# source_eagle.net
KiCad netlist of a schematic drawn in EAGLE
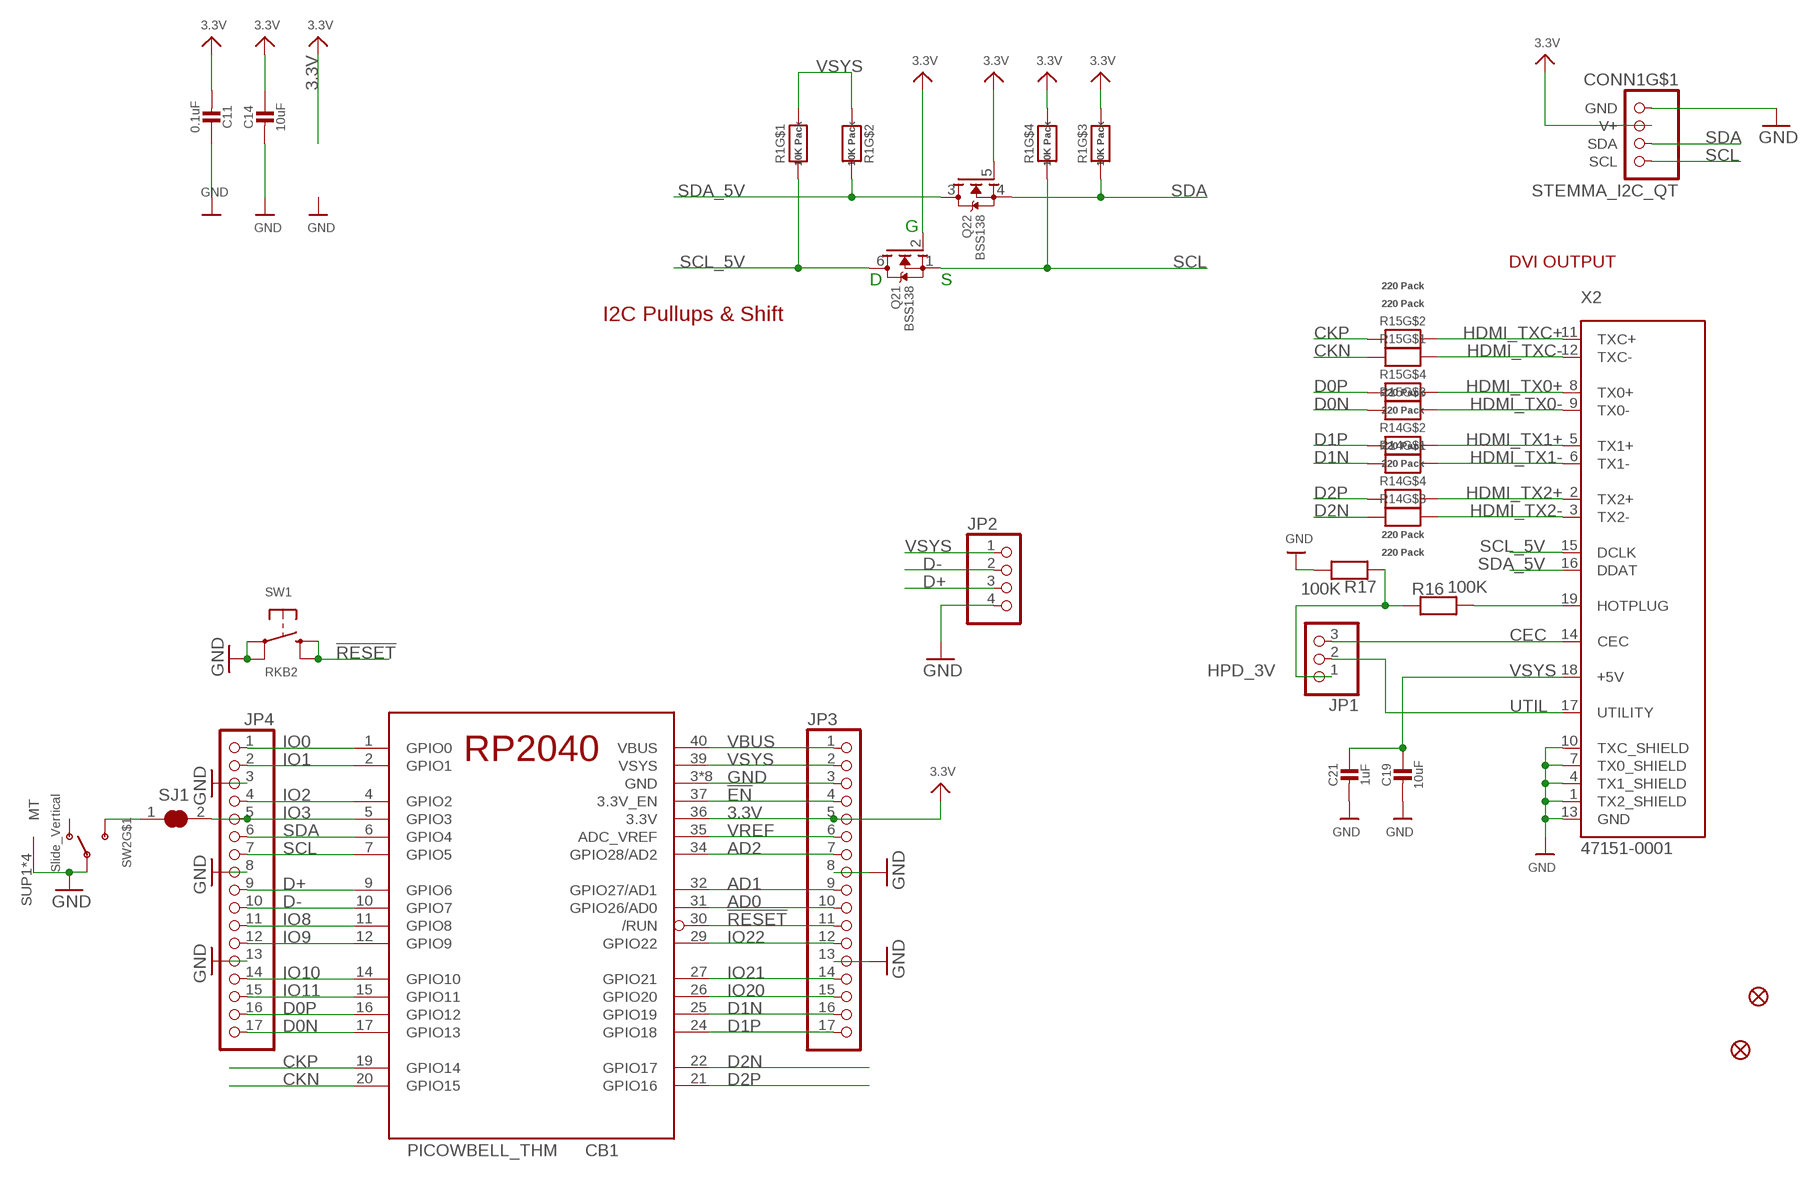
[diagram p0: schematic, sheet 1]

(export (version "E")
  (design (tool "Eeschema 10.0.6"))
  (components
    (comp (ref "C11")
      (value "0.1uF")
      (footprint "eagle-import:0603-NO")
      (libsource (lib "eagle-import") (part "CAP_CERAMIC0603_NO"))
    )
    (comp (ref "C14")
      (value "10uF")
      (footprint "eagle-import:0805-NO")
      (libsource (lib "eagle-import") (part "CAP_CERAMIC0805-NOOUTLINE"))
    )
    (comp (ref "C19")
      (value "10uF")
      (footprint "eagle-import:0805-NO")
      (fields (field (name "REV") "A"))
      (libsource (lib "eagle-import") (part "CAP_CERAMIC0805-NOOUTLINE"))
    )
    (comp (ref "C21")
      (value "1uF")
      (footprint "eagle-import:0603-NO")
      (libsource (lib "eagle-import") (part "CAP_CERAMIC0603_NO"))
    )
    (comp (ref "CB1")
      (value "PICOWBELL_THM")
      (footprint "eagle-import:PICOWBELL_THM")
      (libsource (lib "eagle-import") (part "PICOWBELL_THM"))
    )
    (comp (ref "CONN1")
      (value "STEMMA_I2C_QT")
      (footprint "eagle-import:JST_SH4")
      (libsource (lib "eagle-import") (part "STEMMA_I2C_QT"))
    )
    (comp (ref "FID1")
      (value "FIDUCIAL_1MM")
      (footprint "eagle-import:FIDUCIAL_1MM")
      (libsource (lib "eagle-import") (part "FIDUCIAL_1MM"))
    )
    (comp (ref "FID2")
      (value "FIDUCIAL_1MM")
      (footprint "eagle-import:FIDUCIAL_1MM")
      (libsource (lib "eagle-import") (part "FIDUCIAL_1MM"))
    )
    (comp (ref "JP1")
      (value "HEADER-1X3ROUND")
      (footprint "eagle-import:1X03_ROUND")
      (libsource (lib "eagle-import") (part "HEADER-1X3ROUND"))
    )
    (comp (ref "JP2")
      (value "HEADER-1X4ROUND")
      (footprint "eagle-import:1X04_ROUND")
      (libsource (lib "eagle-import") (part "HEADER-1X4ROUND"))
    )
    (comp (ref "JP3")
      (value "HEADER-1X17")
      (footprint "eagle-import:1X17_ROUND70")
      (libsource (lib "eagle-import") (part "HEADER-1X17"))
    )
    (comp (ref "JP4")
      (value "HEADER-1X17")
      (footprint "eagle-import:1X17_ROUND70")
      (libsource (lib "eagle-import") (part "HEADER-1X17"))
    )
    (comp (ref "Q2")
      (value "BSS138")
      (footprint "eagle-import:SOT363")
      (libsource (lib "eagle-import") (part "MOSFET-N_DUAL"))
    )
    (comp (ref "R1")
      (value "10K Pack")
      (footprint "eagle-import:RESPACK_4X0603")
      (libsource (lib "eagle-import") (part "RESISTOR_4PACK"))
    )
    (comp (ref "R14")
      (value "220 Pack")
      (footprint "eagle-import:RESPACK_4X0603")
      (libsource (lib "eagle-import") (part "RESISTOR_4PACK"))
    )
    (comp (ref "R15")
      (value "220 Pack")
      (footprint "eagle-import:RESPACK_4X0603")
      (libsource (lib "eagle-import") (part "RESISTOR_4PACK"))
    )
    (comp (ref "R16")
      (value "100K")
      (footprint "eagle-import:0603-NO")
      (libsource (lib "eagle-import") (part "RESISTOR_0603_NOOUT"))
    )
    (comp (ref "R17")
      (value "100K")
      (footprint "eagle-import:0603-NO")
      (libsource (lib "eagle-import") (part "RESISTOR_0603_NOOUT"))
    )
    (comp (ref "SJ1")
      (value "SOLDERJUMPER_CLOSED")
      (footprint "eagle-import:SOLDERJUMPER_CLOSEDWIRE")
      (libsource (lib "eagle-import") (part "SOLDERJUMPER_CLOSED"))
    )
    (comp (ref "SW1")
      (value "RKB2")
      (footprint "eagle-import:BTN_RKB2_4.6X2.8")
      (libsource (lib "eagle-import") (part "SWITCH_TACT_SMT_RKB2"))
    )
    (comp (ref "SW2")
      (value "Slide_Vertical")
      (footprint "eagle-import:SPDT_SMT_SSSS811101")
      (libsource (lib "eagle-import") (part "SWITCH_SPDT"))
    )
    (comp (ref "X2")
      (value "47151-0001")
      (footprint "eagle-import:MINIHDMI_CNCTECH")
      (libsource (lib "eagle-import") (part "HDMI_MOLEX_47151_MINI"))
    )
  )
  (nets
    (net (code "1") (name "/AD0") (class "Default")
      (node (ref "CB1") (pin "31") (pinfunction "GPIO26/AD0_31") (pintype "bidirectional"))
      (node (ref "JP3") (pin "10") (pinfunction "10_10") (pintype "passive"))
    )
    (net (code "2") (name "/AD1") (class "Default")
      (node (ref "CB1") (pin "32") (pinfunction "GPIO27/AD1_32") (pintype "bidirectional"))
      (node (ref "JP3") (pin "9") (pinfunction "9_9") (pintype "passive"))
    )
    (net (code "3") (name "/AD2") (class "Default")
      (node (ref "CB1") (pin "34") (pinfunction "GPIO28/AD2_34") (pintype "bidirectional"))
      (node (ref "JP3") (pin "7") (pinfunction "7_7") (pintype "passive"))
    )
    (net (code "4") (name "/CEC") (class "Default")
      (node (ref "JP1") (pin "3") (pinfunction "3_3") (pintype "passive"))
      (node (ref "X2") (pin "14") (pinfunction "CEC_14") (pintype "bidirectional"))
    )
    (net (code "5") (name "/CKN") (class "Default")
      (node (ref "CB1") (pin "20") (pinfunction "GPIO15_20") (pintype "bidirectional"))
      (node (ref "R15") (pin "8") (pinfunction "2_8") (pintype "passive"))
    )
    (net (code "6") (name "/CKP") (class "Default")
      (node (ref "CB1") (pin "19") (pinfunction "GPIO14_19") (pintype "bidirectional"))
      (node (ref "R15") (pin "7") (pinfunction "2_7") (pintype "passive"))
    )
    (net (code "7") (name "/D+") (class "Default")
      (node (ref "CB1") (pin "9") (pinfunction "GPIO6_9") (pintype "bidirectional"))
      (node (ref "JP2") (pin "3") (pinfunction "3_3") (pintype "passive"))
      (node (ref "JP4") (pin "9") (pinfunction "9_9") (pintype "passive"))
    )
    (net (code "8") (name "/D-") (class "Default")
      (node (ref "CB1") (pin "10") (pinfunction "GPIO7_10") (pintype "bidirectional"))
      (node (ref "JP2") (pin "2") (pinfunction "2_2") (pintype "passive"))
      (node (ref "JP4") (pin "10") (pinfunction "10_10") (pintype "passive"))
    )
    (net (code "9") (name "/D0N") (class "Default")
      (node (ref "CB1") (pin "17") (pinfunction "GPIO13_17") (pintype "bidirectional"))
      (node (ref "JP4") (pin "17") (pinfunction "17_17") (pintype "passive"))
      (node (ref "R15") (pin "6") (pinfunction "2_6") (pintype "passive"))
    )
    (net (code "10") (name "/D0P") (class "Default")
      (node (ref "CB1") (pin "16") (pinfunction "GPIO12_16") (pintype "bidirectional"))
      (node (ref "JP4") (pin "16") (pinfunction "16_16") (pintype "passive"))
      (node (ref "R15") (pin "5") (pinfunction "2_5") (pintype "passive"))
    )
    (net (code "11") (name "/D1N") (class "Default")
      (node (ref "CB1") (pin "25") (pinfunction "GPIO19_25") (pintype "bidirectional"))
      (node (ref "JP3") (pin "16") (pinfunction "16_16") (pintype "passive"))
      (node (ref "R14") (pin "8") (pinfunction "2_8") (pintype "passive"))
    )
    (net (code "12") (name "/D1P") (class "Default")
      (node (ref "CB1") (pin "24") (pinfunction "GPIO18_24") (pintype "bidirectional"))
      (node (ref "JP3") (pin "17") (pinfunction "17_17") (pintype "passive"))
      (node (ref "R14") (pin "7") (pinfunction "2_7") (pintype "passive"))
    )
    (net (code "13") (name "/D2N") (class "Default")
      (node (ref "CB1") (pin "22") (pinfunction "GPIO17_22") (pintype "bidirectional"))
      (node (ref "R14") (pin "6") (pinfunction "2_6") (pintype "passive"))
    )
    (net (code "14") (name "/D2P") (class "Default")
      (node (ref "CB1") (pin "21") (pinfunction "GPIO16_21") (pintype "bidirectional"))
      (node (ref "R14") (pin "5") (pinfunction "2_5") (pintype "passive"))
    )
    (net (code "15") (name "/HDMI_TX0+") (class "Default")
      (node (ref "R15") (pin "4") (pinfunction "1_4") (pintype "passive"))
      (node (ref "X2") (pin "8") (pinfunction "TX0+_8") (pintype "bidirectional"))
    )
    (net (code "16") (name "/HDMI_TX0-") (class "Default")
      (node (ref "R15") (pin "3") (pinfunction "1_3") (pintype "passive"))
      (node (ref "X2") (pin "9") (pinfunction "TX0-_9") (pintype "bidirectional"))
    )
    (net (code "17") (name "/HDMI_TX1+") (class "Default")
      (node (ref "R14") (pin "2") (pinfunction "1_2") (pintype "passive"))
      (node (ref "X2") (pin "5") (pinfunction "TX1+_5") (pintype "bidirectional"))
    )
    (net (code "18") (name "/HDMI_TX1-") (class "Default")
      (node (ref "R14") (pin "1") (pinfunction "1_1") (pintype "passive"))
      (node (ref "X2") (pin "6") (pinfunction "TX1-_6") (pintype "bidirectional"))
    )
    (net (code "19") (name "/HDMI_TX2+") (class "Default")
      (node (ref "R14") (pin "4") (pinfunction "1_4") (pintype "passive"))
      (node (ref "X2") (pin "2") (pinfunction "TX2+_2") (pintype "bidirectional"))
    )
    (net (code "20") (name "/HDMI_TX2-") (class "Default")
      (node (ref "R14") (pin "3") (pinfunction "1_3") (pintype "passive"))
      (node (ref "X2") (pin "3") (pinfunction "TX2-_3") (pintype "bidirectional"))
    )
    (net (code "21") (name "/HDMI_TXC+") (class "Default")
      (node (ref "R15") (pin "2") (pinfunction "1_2") (pintype "passive"))
      (node (ref "X2") (pin "11") (pinfunction "TXC+_11") (pintype "bidirectional"))
    )
    (net (code "22") (name "/HDMI_TXC-") (class "Default")
      (node (ref "R15") (pin "1") (pinfunction "1_1") (pintype "passive"))
      (node (ref "X2") (pin "12") (pinfunction "TXC-_12") (pintype "bidirectional"))
    )
    (net (code "23") (name "/HPD_3V") (class "Default")
      (node (ref "JP1") (pin "1") (pinfunction "1_1") (pintype "passive"))
      (node (ref "R16") (pin "1") (pinfunction "1_1") (pintype "passive"))
      (node (ref "R17") (pin "1") (pinfunction "1_1") (pintype "passive"))
    )
    (net (code "24") (name "/IO0") (class "Default")
      (node (ref "CB1") (pin "1") (pinfunction "GPIO0_1") (pintype "bidirectional"))
      (node (ref "JP4") (pin "1") (pinfunction "1_1") (pintype "passive"))
    )
    (net (code "25") (name "/IO1") (class "Default")
      (node (ref "CB1") (pin "2") (pinfunction "GPIO1_2") (pintype "bidirectional"))
      (node (ref "JP4") (pin "2") (pinfunction "2_2") (pintype "passive"))
    )
    (net (code "26") (name "/IO2") (class "Default")
      (node (ref "CB1") (pin "4") (pinfunction "GPIO2_4") (pintype "bidirectional"))
      (node (ref "JP4") (pin "4") (pinfunction "4_4") (pintype "passive"))
    )
    (net (code "27") (name "/IO3") (class "Default")
      (node (ref "CB1") (pin "5") (pinfunction "GPIO3_5") (pintype "bidirectional"))
      (node (ref "JP4") (pin "5") (pinfunction "5_5") (pintype "passive"))
      (node (ref "SJ1") (pin "2") (pinfunction "2_2") (pintype "passive"))
    )
    (net (code "28") (name "/IO8") (class "Default")
      (node (ref "CB1") (pin "11") (pinfunction "GPIO8_11") (pintype "bidirectional"))
      (node (ref "JP4") (pin "11") (pinfunction "11_11") (pintype "passive"))
    )
    (net (code "29") (name "/IO9") (class "Default")
      (node (ref "CB1") (pin "12") (pinfunction "GPIO9_12") (pintype "bidirectional"))
      (node (ref "JP4") (pin "12") (pinfunction "12_12") (pintype "passive"))
    )
    (net (code "30") (name "/IO10") (class "Default")
      (node (ref "CB1") (pin "14") (pinfunction "GPIO10_14") (pintype "bidirectional"))
      (node (ref "JP4") (pin "14") (pinfunction "14_14") (pintype "passive"))
    )
    (net (code "31") (name "/IO11") (class "Default")
      (node (ref "CB1") (pin "15") (pinfunction "GPIO11_15") (pintype "bidirectional"))
      (node (ref "JP4") (pin "15") (pinfunction "15_15") (pintype "passive"))
    )
    (net (code "32") (name "/IO20") (class "Default")
      (node (ref "CB1") (pin "26") (pinfunction "GPIO20_26") (pintype "bidirectional"))
      (node (ref "JP3") (pin "15") (pinfunction "15_15") (pintype "passive"))
    )
    (net (code "33") (name "/IO21") (class "Default")
      (node (ref "CB1") (pin "27") (pinfunction "GPIO21_27") (pintype "bidirectional"))
      (node (ref "JP3") (pin "14") (pinfunction "14_14") (pintype "passive"))
    )
    (net (code "34") (name "/IO22") (class "Default")
      (node (ref "CB1") (pin "29") (pinfunction "GPIO22_29") (pintype "bidirectional"))
      (node (ref "JP3") (pin "12") (pinfunction "12_12") (pintype "passive"))
    )
    (net (code "35") (name "/SCL") (class "Default")
      (node (ref "CB1") (pin "7") (pinfunction "GPIO5_7") (pintype "bidirectional"))
      (node (ref "CONN1") (pin "4") (pinfunction "SCL_4") (pintype "passive"))
      (node (ref "JP4") (pin "7") (pinfunction "7_7") (pintype "passive"))
      (node (ref "Q2") (pin "1") (pinfunction "S_1") (pintype "bidirectional"))
      (node (ref "R1") (pin "4") (pinfunction "1_4") (pintype "passive"))
    )
    (net (code "36") (name "/SCL_5V") (class "Default")
      (node (ref "Q2") (pin "6") (pinfunction "D_6") (pintype "bidirectional"))
      (node (ref "R1") (pin "8") (pinfunction "2_8") (pintype "passive"))
      (node (ref "X2") (pin "15") (pinfunction "DCLK_15") (pintype "bidirectional"))
    )
    (net (code "37") (name "/SDA") (class "Default")
      (node (ref "CB1") (pin "6") (pinfunction "GPIO4_6") (pintype "bidirectional"))
      (node (ref "CONN1") (pin "3") (pinfunction "SDA_3") (pintype "passive"))
      (node (ref "JP4") (pin "6") (pinfunction "6_6") (pintype "passive"))
      (node (ref "Q2") (pin "4") (pinfunction "S_4") (pintype "bidirectional"))
      (node (ref "R1") (pin "3") (pinfunction "1_3") (pintype "passive"))
    )
    (net (code "38") (name "/SDA_5V") (class "Default")
      (node (ref "Q2") (pin "3") (pinfunction "D_3") (pintype "bidirectional"))
      (node (ref "R1") (pin "7") (pinfunction "2_7") (pintype "passive"))
      (node (ref "X2") (pin "16") (pinfunction "DDAT_16") (pintype "bidirectional"))
    )
    (net (code "39") (name "/UTIL") (class "Default")
      (node (ref "JP1") (pin "2") (pinfunction "2_2") (pintype "passive"))
      (node (ref "X2") (pin "17") (pinfunction "UTILITY_17") (pintype "bidirectional"))
    )
    (net (code "40") (name "/VBUS") (class "Default")
      (node (ref "CB1") (pin "40") (pinfunction "VBUS_40") (pintype "power_in"))
      (node (ref "JP3") (pin "1") (pinfunction "1_1") (pintype "passive"))
    )
    (net (code "41") (name "/VREF") (class "Default")
      (node (ref "CB1") (pin "35") (pinfunction "ADC_VREF_35") (pintype "passive"))
      (node (ref "JP3") (pin "6") (pinfunction "6_6") (pintype "passive"))
    )
    (net (code "42") (name "/VSYS") (class "Default")
      (node (ref "C19") (pin "1") (pinfunction "1_1") (pintype "passive"))
      (node (ref "C21") (pin "1") (pinfunction "1_1") (pintype "passive"))
      (node (ref "CB1") (pin "39") (pinfunction "VSYS_39") (pintype "power_in"))
      (node (ref "JP2") (pin "1") (pinfunction "1_1") (pintype "passive"))
      (node (ref "JP3") (pin "2") (pinfunction "2_2") (pintype "passive"))
      (node (ref "R1") (pin "1") (pinfunction "1_1") (pintype "passive"))
      (node (ref "R1") (pin "2") (pinfunction "1_2") (pintype "passive"))
      (node (ref "X2") (pin "18") (pinfunction "+5V_18") (pintype "power_in"))
    )
    (net (code "43") (name "/~{EN}") (class "Default")
      (node (ref "CB1") (pin "37") (pinfunction "3.3V_EN_37") (pintype "passive"))
      (node (ref "JP3") (pin "4") (pinfunction "4_4") (pintype "passive"))
    )
    (net (code "44") (name "/~{RESET}") (class "Default")
      (node (ref "CB1") (pin "30") (pinfunction "/RUN_30") (pintype "bidirectional"))
      (node (ref "JP3") (pin "11") (pinfunction "11_11") (pintype "passive"))
      (node (ref "SW1") (pin "B") (pinfunction "S_B") (pintype "passive"))
      (node (ref "SW1") (pin "B'") (pinfunction "S1_B'") (pintype "passive"))
    )
    (net (code "45") (name "3.3V") (class "Default")
      (node (ref "C11") (pin "2") (pinfunction "2_2") (pintype "passive"))
      (node (ref "C14") (pin "1") (pinfunction "1_1") (pintype "passive"))
      (node (ref "CB1") (pin "36") (pinfunction "3.3V_36") (pintype "power_in"))
      (node (ref "CONN1") (pin "2") (pinfunction "V+_2") (pintype "passive"))
      (node (ref "JP3") (pin "5") (pinfunction "5_5") (pintype "passive"))
      (node (ref "Q2") (pin "2") (pinfunction "G_2") (pintype "bidirectional"))
      (node (ref "Q2") (pin "5") (pinfunction "G_5") (pintype "bidirectional"))
      (node (ref "R1") (pin "5") (pinfunction "2_5") (pintype "passive"))
      (node (ref "R1") (pin "6") (pinfunction "2_6") (pintype "passive"))
    )
    (net (code "46") (name "GND") (class "Default")
      (node (ref "C11") (pin "1") (pinfunction "1_1") (pintype "passive"))
      (node (ref "C14") (pin "2") (pinfunction "2_2") (pintype "passive"))
      (node (ref "C19") (pin "2") (pinfunction "2_2") (pintype "passive"))
      (node (ref "C21") (pin "2") (pinfunction "2_2") (pintype "passive"))
      (node (ref "CB1") (pin "13") (pinfunction "GND_13") (pintype "power_in"))
      (node (ref "CB1") (pin "18") (pinfunction "GND_18") (pintype "power_in"))
      (node (ref "CB1") (pin "23") (pinfunction "GND_23") (pintype "power_in"))
      (node (ref "CB1") (pin "28") (pinfunction "GND_28") (pintype "power_in"))
      (node (ref "CB1") (pin "3") (pinfunction "GND_3") (pintype "power_in"))
      (node (ref "CB1") (pin "33") (pinfunction "GND_33") (pintype "power_in"))
      (node (ref "CB1") (pin "38") (pinfunction "GND_38") (pintype "power_in"))
      (node (ref "CB1") (pin "8") (pinfunction "GND_8") (pintype "power_in"))
      (node (ref "CONN1") (pin "1") (pinfunction "GND_1") (pintype "passive"))
      (node (ref "JP2") (pin "4") (pinfunction "4_4") (pintype "passive"))
      (node (ref "JP3") (pin "13") (pinfunction "13_13") (pintype "passive"))
      (node (ref "JP3") (pin "3") (pinfunction "3_3") (pintype "passive"))
      (node (ref "JP3") (pin "8") (pinfunction "8_8") (pintype "passive"))
      (node (ref "JP4") (pin "13") (pinfunction "13_13") (pintype "passive"))
      (node (ref "JP4") (pin "3") (pinfunction "3_3") (pintype "passive"))
      (node (ref "JP4") (pin "8") (pinfunction "8_8") (pintype "passive"))
      (node (ref "R17") (pin "2") (pinfunction "2_2") (pintype "passive"))
      (node (ref "SW1") (pin "A") (pinfunction "P_A") (pintype "passive"))
      (node (ref "SW1") (pin "A'") (pinfunction "P1_A'") (pintype "passive"))
      (node (ref "SW2") (pin "B") (pinfunction "P_B") (pintype "passive"))
      (node (ref "SW2") (pin "SUP1") (pinfunction "MT_SUP1") (pintype "bidirectional"))
      (node (ref "SW2") (pin "SUP2") (pinfunction "MT_SUP2") (pintype "bidirectional"))
      (node (ref "SW2") (pin "SUP3") (pinfunction "MT_SUP3") (pintype "bidirectional"))
      (node (ref "SW2") (pin "SUP4") (pinfunction "MT_SUP4") (pintype "bidirectional"))
      (node (ref "X2") (pin "1") (pinfunction "TX2_SHIELD_1") (pintype "power_in"))
      (node (ref "X2") (pin "10") (pinfunction "TXC_SHIELD_10") (pintype "power_in"))
      (node (ref "X2") (pin "13") (pinfunction "GND_13") (pintype "power_in"))
      (node (ref "X2") (pin "4") (pinfunction "TX1_SHIELD_4") (pintype "power_in"))
      (node (ref "X2") (pin "7") (pinfunction "TX0_SHIELD_7") (pintype "power_in"))
    )
    (net (code "47") (name "Net-(SW2A-S)") (class "Default")
      (node (ref "SJ1") (pin "1") (pinfunction "1_1") (pintype "passive"))
      (node (ref "SW2") (pin "C") (pinfunction "S_C") (pintype "passive"))
    )
    (net (code "48") (name "Net-(X2A-HOTPLUG)") (class "Default")
      (node (ref "R16") (pin "2") (pinfunction "2_2") (pintype "passive"))
      (node (ref "X2") (pin "19") (pinfunction "HOTPLUG_19") (pintype "bidirectional"))
    )
    (net (code "49") (name "unconnected-(SW2A-O-PadA)") (class "Default")
      (node (ref "SW2") (pin "A") (pinfunction "O_A") (pintype "passive"))
    )
  )
)
